# Photodiode_Receiver.net
KiCad netlist of a schematic drawn in Altium Designer
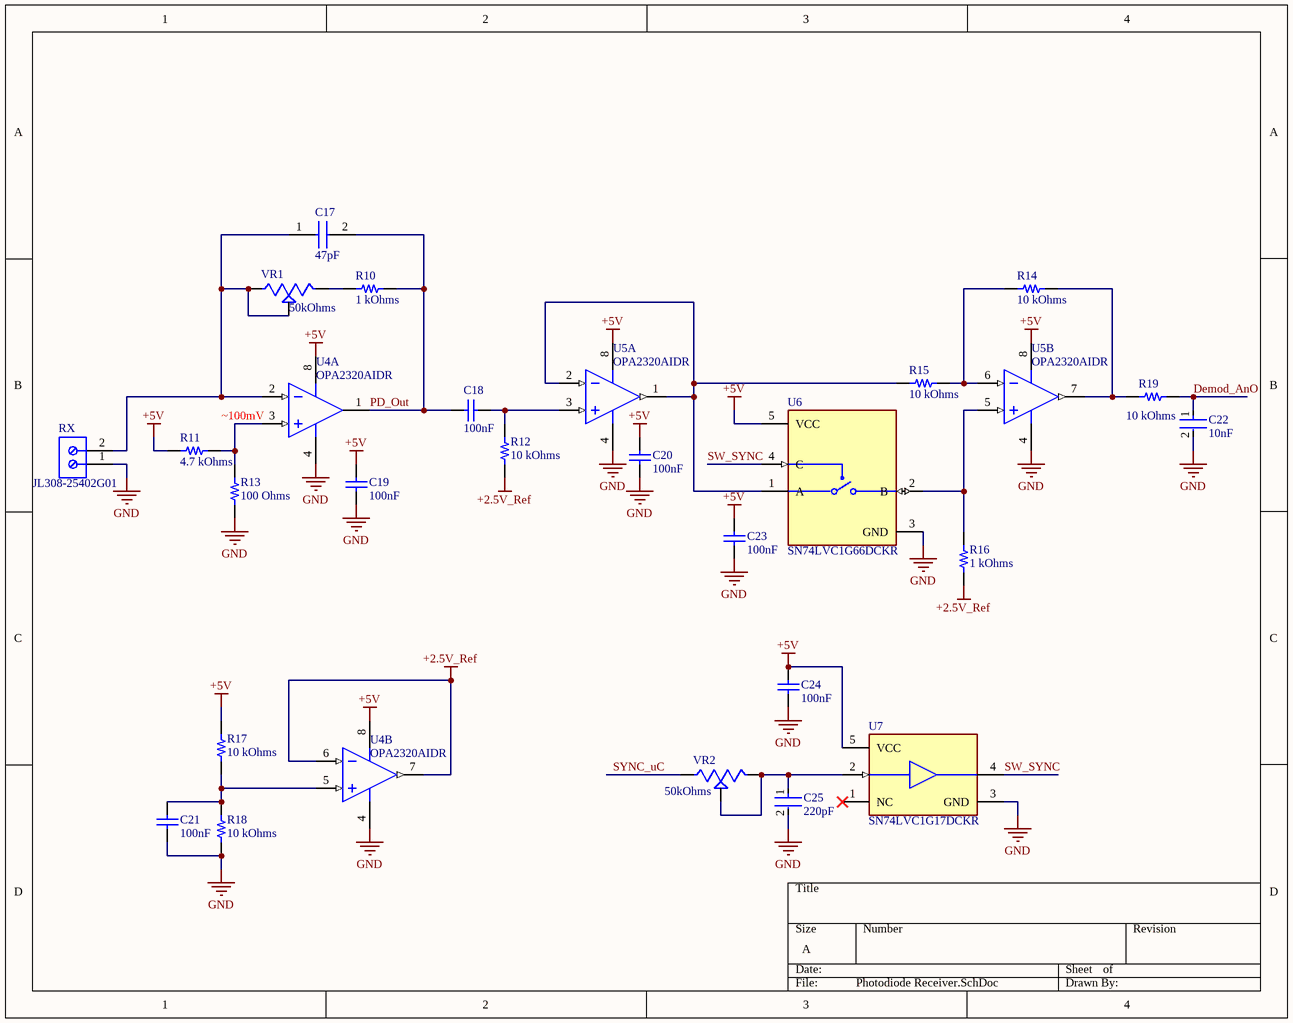
[diagram p0: Photodiode Receiver.SchDoc]

(export (version "E")
  (design (tool "Eeschema 10.0.6"))
  (components
    (comp (ref "C17")
      (value "47pF")
      (footprint "SamacSys:CAPC1005X55N")
      (description "Capacitor 0402CG470J500NT")
      (fields (field (name "MANUFACTURER_PART_NUMBER") "0402CG470J500NT"))
      (libsource (lib "*") (part "0402CG470J500NT"))
    )
    (comp (ref "C18")
      (value "100nF")
      (footprint "CAPC1050X55X23ML05T13")
      (description "Chip Capacitor, 100 nF, +/- 10%, 16 V, -55 to 125 degC, 0402 (1005 Metric), RoHS, Tape and Reel")
      (fields (field (name "MANUFACTURER") "Samsung Electro-Mechanics"))
      (libsource (lib "Altium Content Vault") (part "CAP-NP-2"))
    )
    (comp (ref "C19")
      (value "100nF")
      (footprint "CAPC1050X55X23ML05T13")
      (description "Chip Capacitor, 100 nF, +/- 10%, 16 V, -55 to 125 degC, 0402 (1005 Metric), RoHS, Tape and Reel")
      (fields (field (name "MANUFACTURER") "Samsung Electro-Mechanics"))
      (libsource (lib "Altium Content Vault") (part "CAP-NP-2"))
    )
    (comp (ref "C20")
      (value "100nF")
      (footprint "CAPC1050X55X23ML05T13")
      (description "Chip Capacitor, 100 nF, +/- 10%, 16 V, -55 to 125 degC, 0402 (1005 Metric), RoHS, Tape and Reel")
      (fields (field (name "MANUFACTURER") "Samsung Electro-Mechanics"))
      (libsource (lib "Altium Content Vault") (part "CAP-NP-2"))
    )
    (comp (ref "C21")
      (value "100nF")
      (footprint "CAPC1050X55X23ML05T13")
      (description "Chip Capacitor, 100 nF, +/- 10%, 16 V, -55 to 125 degC, 0402 (1005 Metric), RoHS, Tape and Reel")
      (fields (field (name "MANUFACTURER") "Samsung Electro-Mechanics"))
      (libsource (lib "Altium Content Vault") (part "CAP-NP-2"))
    )
    (comp (ref "C22")
      (value "10nF")
      (footprint "FP-CL165-IPC_C")
      (description "Cap Ceramic 10nF 50V X7R ±10% SMD 0402 +125°C Paper T/R")
      (fields (field (name "VOLTAGE") "50V") (field (name "TOLERANCE") "10%"))
      (libsource (lib "Altium Content Vault") (part "b4654b650e69147ec39a6b967a45e02"))
    )
    (comp (ref "C23")
      (value "100nF")
      (footprint "CAPC1050X55X23ML05T13")
      (description "Chip Capacitor, 100 nF, +/- 10%, 16 V, -55 to 125 degC, 0402 (1005 Metric), RoHS, Tape and Reel")
      (fields (field (name "MANUFACTURER") "Samsung Electro-Mechanics"))
      (libsource (lib "Altium Content Vault") (part "CAP-NP-2"))
    )
    (comp (ref "C24")
      (value "100nF")
      (footprint "CAPC1050X55X23ML05T13")
      (description "Chip Capacitor, 100 nF, +/- 10%, 16 V, -55 to 125 degC, 0402 (1005 Metric), RoHS, Tape and Reel")
      (fields (field (name "MANUFACTURER") "Samsung Electro-Mechanics"))
      (libsource (lib "Altium Content Vault") (part "CAP-NP-2"))
    )
    (comp (ref "C25")
      (value "220pF")
      (footprint "FP-CL10-IPC_A")
      (description "Cap Ceramic 220pF 50V X7R ±10% Pad SMD 0603 +125°C T/R")
      (fields (field (name "TOLERANCE") "10%") (field (name "VOLTAGE") "50V"))
      (libsource (lib "Altium Content Vault") (part "b4654b650e69147ec39a6b967a45e02"))
    )
    (comp (ref "R10")
      (value "1 kOhms")
      (footprint "RES 0402_1005")
      (description "RES SMD 1K OHM 0.1% 1/16W 0402")
      (fields
        (field (name "PART NUMBER") "CPF0402B1K0E")
        (field (name "MANUFACTURER") "TE Connectivity Passive Product")
      )
      (libsource (lib "Celestial Altium Library - altium_library") (part "Resistor"))
    )
    (comp (ref "R11")
      (value "4.7 kOhms")
      (footprint "RES 0402_1005")
      (description "RES SMD 4.7K OHM 0.5% 1/16W 0402")
      (fields (field (name "PART NUMBER") "RR0510P-472-D") (field (name "MANUFACTURER") "Susumu"))
      (libsource (lib "Celestial Altium Library - altium_library") (part "Resistor"))
    )
    (comp (ref "R12")
      (value "10 kOhms")
      (footprint "RES 0402_1005")
      (description "RES SMD 10K OHM 1% 1/16W 0402")
      (fields (field (name "PART NUMBER") "CRCW040210K0FKEE") (field (name "MANUFACTURER") "Vishay Dale"))
      (libsource (lib "Celestial Altium Library - altium_library") (part "Resistor"))
    )
    (comp (ref "R13")
      (value "100 Ohms")
      (footprint "RES 0402_1005")
      (description "RES SMD 100 OHM 0.5% 1/16W 0402")
      (fields (field (name "PART NUMBER") "RR0510P-101-D") (field (name "MANUFACTURER") "Susumu"))
      (libsource (lib "Celestial Altium Library - altium_library") (part "Resistor"))
    )
    (comp (ref "R14")
      (value "10 kOhms")
      (footprint "RES 0402_1005")
      (description "RES SMD 10K OHM 1% 1/16W 0402")
      (fields (field (name "PART NUMBER") "CRCW040210K0FKEE") (field (name "MANUFACTURER") "Vishay Dale"))
      (libsource (lib "Celestial Altium Library - altium_library") (part "Resistor"))
    )
    (comp (ref "R15")
      (value "10 kOhms")
      (footprint "RES 0402_1005")
      (description "RES SMD 10K OHM 1% 1/16W 0402")
      (fields (field (name "PART NUMBER") "CRCW040210K0FKEE") (field (name "MANUFACTURER") "Vishay Dale"))
      (libsource (lib "Celestial Altium Library - altium_library") (part "Resistor"))
    )
    (comp (ref "R16")
      (value "1 kOhms")
      (footprint "RES 0402_1005")
      (description "RES SMD 1K OHM 0.1% 1/16W 0402")
      (fields
        (field (name "PART NUMBER") "CPF0402B1K0E")
        (field (name "MANUFACTURER") "TE Connectivity Passive Product")
      )
      (libsource (lib "Celestial Altium Library - altium_library") (part "Resistor"))
    )
    (comp (ref "R17")
      (value "10 kOhms")
      (footprint "RES 0402_1005")
      (description "RES SMD 10K OHM 1% 1/16W 0402")
      (fields (field (name "PART NUMBER") "CRCW040210K0FKEE") (field (name "MANUFACTURER") "Vishay Dale"))
      (libsource (lib "Celestial Altium Library - altium_library") (part "Resistor"))
    )
    (comp (ref "R18")
      (value "10 kOhms")
      (footprint "RES 0402_1005")
      (description "RES SMD 10K OHM 1% 1/16W 0402")
      (fields (field (name "PART NUMBER") "CRCW040210K0FKEE") (field (name "MANUFACTURER") "Vishay Dale"))
      (libsource (lib "Celestial Altium Library - altium_library") (part "Resistor"))
    )
    (comp (ref "R19")
      (value "10 kOhms")
      (footprint "RES 0402_1005")
      (description "RES SMD 10K OHM 1% 1/16W 0402")
      (fields (field (name "PART NUMBER") "CRCW040210K0FKEE") (field (name "MANUFACTURER") "Vishay Dale"))
      (libsource (lib "Celestial Altium Library - altium_library") (part "Resistor"))
    )
    (comp (ref "RX")
      (value "JL308-25402G01")
      (footprint "691210910002")
      (description "Use comment for part number")
      (libsource (lib "Altium Content Vault") (part "TBL - 1R - 02P - Screw"))
    )
    (comp (ref "U4")
      (value "OPA2320AIDR")
      (footprint "D0008A_L")
      (fields (field (name "MANUFACTURER") "Texas Instruments"))
      (libsource (lib "Altium Content Vault") (part "TI-OPA-8_2"))
    )
    (comp (ref "U5")
      (value "OPA2320AIDR")
      (footprint "D0008A_L")
      (fields (field (name "MANUFACTURER") "Texas Instruments"))
      (libsource (lib "Altium Content Vault") (part "TI-OPA-8_2"))
    )
    (comp (ref "U6")
      (value "SN74LVC1G66DCKR")
      (footprint "FP-DCK0005A-MFG")
      (description "IC SWITCH 1X1 SC70-5")
      (fields
        (field (name "MANUFACTURER") "Texas Instruments")
        (field (name "OCTOPART") "https://octopart.com/sn74lvc1g66dckr-texas+instruments-472215")
      )
      (libsource (lib "Altium Content Vault") (part "23eca40f027367fc3ff70b4f4715f36"))
    )
    (comp (ref "U7")
      (value "SN74LVC1G17DCKR")
      (footprint "FP-DCK0005A-MFG")
      (description "IC BUF NON-INVERT 5.5V SC70-5")
      (libsource (lib "Altium Content Vault") (part "333895c48767551a2a38df23237d11a"))
    )
    (comp (ref "VR1")
      (value "50kOhms")
      (footprint "TRIM_3314J-1-503E")
      (description "Trimmer, Cermet, Rest 50 Kilohms, SMD, 1 Turn, Pwr-Rtg 0.25W ¦ Bourns 3314J-1-503E")
      (fields (field (name "MF") "Bourns") (field (name "MP") "3314J-1-503E"))
      (libsource (lib "3314J-1-503E") (part "3314J-1-503E"))
    )
    (comp (ref "VR2")
      (value "50kOhms")
      (footprint "TRIM_3314J-1-503E")
      (description "Trimmer, Cermet, Rest 50 Kilohms, SMD, 1 Turn, Pwr-Rtg 0.25W ¦ Bourns 3314J-1-503E")
      (fields (field (name "MF") "Bourns") (field (name "MP") "3314J-1-503E"))
      (libsource (lib "3314J-1-503E") (part "3314J-1-503E"))
    )
  )
  (nets
    (net (code "1") (name "+2.5V_Ref") (class "Default")
      (node (ref "R12") (pin "1") (pinfunction "1_1") (pintype "passive"))
      (node (ref "R16") (pin "2") (pinfunction "2_2") (pintype "passive"))
      (node (ref "U4") (pin "6") (pinfunction "IN_B-_6") (pintype "input"))
      (node (ref "U4") (pin "7") (pinfunction "OUT_B_7") (pintype "output"))
    )
    (net (code "2") (name "+5V") (class "Default")
      (node (ref "C19") (pin "2") (pinfunction "2_2") (pintype "passive"))
      (node (ref "C20") (pin "2") (pinfunction "2_2") (pintype "passive"))
      (node (ref "C23") (pin "2") (pinfunction "2_2") (pintype "passive"))
      (node (ref "C24") (pin "2") (pinfunction "2_2") (pintype "passive"))
      (node (ref "R11") (pin "1") (pinfunction "1_1") (pintype "passive"))
      (node (ref "R17") (pin "2") (pinfunction "2_2") (pintype "passive"))
      (node (ref "U4") (pin "8") (pinfunction "V+_8") (pintype "power_in"))
      (node (ref "U5") (pin "8") (pinfunction "V+_8") (pintype "power_in"))
      (node (ref "U6") (pin "5") (pinfunction "VCC_5") (pintype "power_in"))
      (node (ref "U7") (pin "5") (pinfunction "VCC_5") (pintype "power_in"))
    )
    (net (code "3") (name "/Demod_AnO") (class "Default")
      (node (ref "C22") (pin "1") (pinfunction "1_1") (pintype "passive"))
      (node (ref "R19") (pin "1") (pinfunction "1_1") (pintype "passive"))
    )
    (net (code "4") (name "/PD_Out") (class "Default")
      (node (ref "C17") (pin "2") (pinfunction "2_2") (pintype "passive"))
      (node (ref "C18") (pin "2") (pinfunction "2_2") (pintype "passive"))
      (node (ref "R10") (pin "1") (pinfunction "1_1") (pintype "passive"))
      (node (ref "U4") (pin "1") (pinfunction "OUT_A_1") (pintype "output"))
    )
    (net (code "5") (name "/SW_SYNC") (class "Default")
      (node (ref "U6") (pin "4") (pinfunction "C_4") (pintype "input"))
      (node (ref "U7") (pin "4") (pinfunction "Y_4") (pintype "passive"))
    )
    (net (code "6") (name "/SYNC_uC") (class "Default")
      (node (ref "VR2") (pin "3") (pinfunction "CW_3") (pintype "passive"))
    )
    (net (code "7") (name "GND") (class "Default")
      (node (ref "C19") (pin "1") (pinfunction "1_1") (pintype "passive"))
      (node (ref "C20") (pin "1") (pinfunction "1_1") (pintype "passive"))
      (node (ref "C21") (pin "1") (pinfunction "1_1") (pintype "passive"))
      (node (ref "C22") (pin "2") (pinfunction "2_2") (pintype "passive"))
      (node (ref "C23") (pin "1") (pinfunction "1_1") (pintype "passive"))
      (node (ref "C24") (pin "1") (pinfunction "1_1") (pintype "passive"))
      (node (ref "C25") (pin "2") (pinfunction "2_2") (pintype "passive"))
      (node (ref "R13") (pin "1") (pinfunction "1_1") (pintype "passive"))
      (node (ref "R18") (pin "1") (pinfunction "1_1") (pintype "passive"))
      (node (ref "RX") (pin "1") (pinfunction "1_1") (pintype "passive"))
      (node (ref "U4") (pin "4") (pinfunction "V-_4") (pintype "power_in"))
      (node (ref "U5") (pin "4") (pinfunction "V-_4") (pintype "power_in"))
      (node (ref "U6") (pin "3") (pinfunction "GND_3") (pintype "power_in"))
      (node (ref "U7") (pin "3") (pinfunction "GND_3") (pintype "power_in"))
    )
    (net (code "8") (name "Net-(U4A-IN_A+)") (class "Default")
      (node (ref "R11") (pin "2") (pinfunction "2_2") (pintype "passive"))
      (node (ref "R13") (pin "2") (pinfunction "2_2") (pintype "passive"))
      (node (ref "U4") (pin "3") (pinfunction "IN_A+_3") (pintype "input"))
    )
    (net (code "9") (name "Net-(U4A-IN_A-)") (class "Default")
      (node (ref "C17") (pin "1") (pinfunction "1_1") (pintype "passive"))
      (node (ref "RX") (pin "2") (pinfunction "2_2") (pintype "passive"))
      (node (ref "U4") (pin "2") (pinfunction "IN_A-_2") (pintype "input"))
      (node (ref "VR1") (pin "2") (pinfunction "WIPER_2") (pintype "passive"))
      (node (ref "VR1") (pin "3") (pinfunction "CW_3") (pintype "passive"))
    )
    (net (code "10") (name "Net-(U4B-IN_B+)") (class "Default")
      (node (ref "C21") (pin "2") (pinfunction "2_2") (pintype "passive"))
      (node (ref "R17") (pin "1") (pinfunction "1_1") (pintype "passive"))
      (node (ref "R18") (pin "2") (pinfunction "2_2") (pintype "passive"))
      (node (ref "U4") (pin "5") (pinfunction "IN_B+_5") (pintype "input"))
    )
    (net (code "11") (name "Net-(U5A-IN_A+)") (class "Default")
      (node (ref "C18") (pin "1") (pinfunction "1_1") (pintype "passive"))
      (node (ref "R12") (pin "2") (pinfunction "2_2") (pintype "passive"))
      (node (ref "U5") (pin "3") (pinfunction "IN_A+_3") (pintype "input"))
    )
    (net (code "12") (name "Net-(U5A-IN_A-)") (class "Default")
      (node (ref "R15") (pin "2") (pinfunction "2_2") (pintype "passive"))
      (node (ref "U5") (pin "1") (pinfunction "OUT_A_1") (pintype "output"))
      (node (ref "U5") (pin "2") (pinfunction "IN_A-_2") (pintype "input"))
      (node (ref "U6") (pin "1") (pinfunction "A_1") (pintype "passive"))
    )
    (net (code "13") (name "Net-(U5B-IN_B+)") (class "Default")
      (node (ref "R16") (pin "1") (pinfunction "1_1") (pintype "passive"))
      (node (ref "U5") (pin "5") (pinfunction "IN_B+_5") (pintype "input"))
      (node (ref "U6") (pin "2") (pinfunction "B_2") (pintype "bidirectional"))
    )
    (net (code "14") (name "Net-(U5B-IN_B-)") (class "Default")
      (node (ref "R14") (pin "2") (pinfunction "2_2") (pintype "passive"))
      (node (ref "R15") (pin "1") (pinfunction "1_1") (pintype "passive"))
      (node (ref "U5") (pin "6") (pinfunction "IN_B-_6") (pintype "input"))
    )
    (net (code "15") (name "Net-(U5B-OUT_B)") (class "Default")
      (node (ref "R14") (pin "1") (pinfunction "1_1") (pintype "passive"))
      (node (ref "R19") (pin "2") (pinfunction "2_2") (pintype "passive"))
      (node (ref "U5") (pin "7") (pinfunction "OUT_B_7") (pintype "output"))
    )
    (net (code "16") (name "Net-(U7-A)") (class "Default")
      (node (ref "C25") (pin "1") (pinfunction "1_1") (pintype "passive"))
      (node (ref "U7") (pin "2") (pinfunction "A_2") (pintype "input"))
      (node (ref "VR2") (pin "1") (pinfunction "CCW_1") (pintype "passive"))
      (node (ref "VR2") (pin "2") (pinfunction "WIPER_2") (pintype "passive"))
    )
    (net (code "17") (name "Net-(VR1-CCW)") (class "Default")
      (node (ref "R10") (pin "2") (pinfunction "2_2") (pintype "passive"))
      (node (ref "VR1") (pin "1") (pinfunction "CCW_1") (pintype "passive"))
    )
    (net (code "18") (name "unconnected-(U7-NC-Pad1)") (class "Default")
      (node (ref "U7") (pin "1") (pinfunction "NC_1") (pintype "passive+no_connect"))
    )
  )
)
